# usb_r2.net
KiCad netlist of a schematic drawn in EAGLE
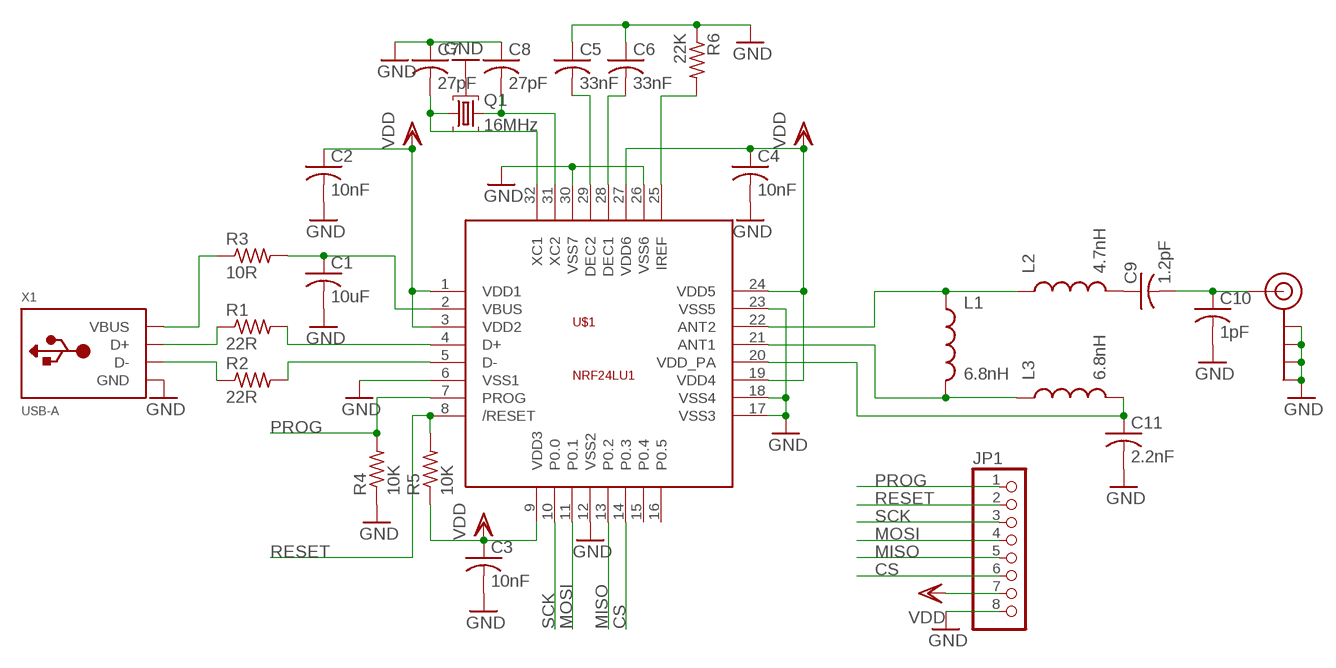
[diagram p0: schematic, sheet 1]

(export (version "E")
  (design (tool "Eeschema 10.0.6"))
  (components
    (comp (ref "C1")
      (value "10uF")
      (footprint "eagle-import:C0805K")
      (libsource (lib "eagle-import") (part "C-USC0805K"))
    )
    (comp (ref "C2")
      (value "10nF")
      (footprint "eagle-import:C0402")
      (libsource (lib "eagle-import") (part "C-USC0402"))
    )
    (comp (ref "C3")
      (value "10nF")
      (footprint "eagle-import:C0402")
      (libsource (lib "eagle-import") (part "C-USC0402"))
    )
    (comp (ref "C4")
      (value "10nF")
      (footprint "eagle-import:C0402")
      (libsource (lib "eagle-import") (part "C-USC0402"))
    )
    (comp (ref "C5")
      (value "33nF")
      (footprint "eagle-import:C0402")
      (libsource (lib "eagle-import") (part "C-USC0402"))
    )
    (comp (ref "C6")
      (value "33nF")
      (footprint "eagle-import:C0402")
      (libsource (lib "eagle-import") (part "C-USC0402"))
    )
    (comp (ref "C7")
      (value "27pF")
      (footprint "eagle-import:C0402")
      (libsource (lib "eagle-import") (part "C-USC0402"))
    )
    (comp (ref "C8")
      (value "27pF")
      (footprint "eagle-import:C0402")
      (libsource (lib "eagle-import") (part "C-USC0402"))
    )
    (comp (ref "C9")
      (value "1.2pF")
      (footprint "eagle-import:C0402")
      (libsource (lib "eagle-import") (part "C-USC0402"))
    )
    (comp (ref "C10")
      (value "1pF")
      (footprint "eagle-import:C0402")
      (libsource (lib "eagle-import") (part "C-USC0402"))
    )
    (comp (ref "C11")
      (value "2.2nF")
      (footprint "eagle-import:C0402")
      (libsource (lib "eagle-import") (part "C-USC0402"))
    )
    (comp (ref "J$1")
      (value "SMA_EDGE")
      (footprint "eagle-import:SMA-EDGE")
      (libsource (lib "eagle-import") (part "SMA_EDGE"))
    )
    (comp (ref "JP1")
      (value "PINHD-1X8")
      (footprint "eagle-import:1X08")
      (libsource (lib "eagle-import") (part "PINHD-1X8"))
    )
    (comp (ref "L1")
      (value "6.8nH")
      (footprint "eagle-import:C0402")
      (libsource (lib "eagle-import") (part "INDUCTOR0402"))
    )
    (comp (ref "L2")
      (value "4.7nH")
      (footprint "eagle-import:C0402")
      (libsource (lib "eagle-import") (part "INDUCTOR0402"))
    )
    (comp (ref "L3")
      (value "6.8nH")
      (footprint "eagle-import:C0402")
      (libsource (lib "eagle-import") (part "INDUCTOR0402"))
    )
    (comp (ref "Q1")
      (value "16MHz")
      (footprint "eagle-import:TSX-3225")
      (libsource (lib "eagle-import") (part "TSX-3225"))
    )
    (comp (ref "R1")
      (value "22R")
      (footprint "eagle-import:R0402")
      (libsource (lib "eagle-import") (part "R-US_R0402"))
    )
    (comp (ref "R2")
      (value "22R")
      (footprint "eagle-import:R0402")
      (libsource (lib "eagle-import") (part "R-US_R0402"))
    )
    (comp (ref "R3")
      (value "10R")
      (footprint "eagle-import:R0402")
      (libsource (lib "eagle-import") (part "R-US_R0402"))
    )
    (comp (ref "R4")
      (value "10K")
      (footprint "eagle-import:R0402")
      (libsource (lib "eagle-import") (part "R-US_R0402"))
    )
    (comp (ref "R5")
      (value "10K")
      (footprint "eagle-import:R0402")
      (libsource (lib "eagle-import") (part "R-US_R0402"))
    )
    (comp (ref "R6")
      (value "22K")
      (footprint "eagle-import:R0402")
      (libsource (lib "eagle-import") (part "R-US_R0402"))
    )
    (comp (ref "U$1")
      (value "NRF24LU1")
      (footprint "eagle-import:QFN-32")
      (libsource (lib "eagle-import") (part "NRF24LU1"))
    )
    (comp (ref "X1")
      (value "USB-A")
      (footprint "eagle-import:MOLEX_480371000")
      (libsource (lib "eagle-import") (part "USB-A"))
    )
  )
  (nets
    (net (code "1") (name "/CS") (class "Default")
      (node (ref "JP1") (pin "6") (pinfunction "6_6") (pintype "passive"))
      (node (ref "U$1") (pin "14") (pinfunction "P0.3_14") (pintype "bidirectional"))
    )
    (net (code "2") (name "/MISO") (class "Default")
      (node (ref "JP1") (pin "5") (pinfunction "5_5") (pintype "passive"))
      (node (ref "U$1") (pin "13") (pinfunction "P0.2_13") (pintype "bidirectional"))
    )
    (net (code "3") (name "/MOSI") (class "Default")
      (node (ref "JP1") (pin "4") (pinfunction "4_4") (pintype "passive"))
      (node (ref "U$1") (pin "11") (pinfunction "P0.1_11") (pintype "bidirectional"))
    )
    (net (code "4") (name "/PROG") (class "Default")
      (node (ref "JP1") (pin "1") (pinfunction "1_1") (pintype "passive"))
      (node (ref "R4") (pin "2") (pinfunction "2_2") (pintype "passive"))
      (node (ref "U$1") (pin "7") (pinfunction "PROG_7") (pintype "bidirectional"))
    )
    (net (code "5") (name "/RESET") (class "Default")
      (node (ref "JP1") (pin "2") (pinfunction "2_2") (pintype "passive"))
      (node (ref "R5") (pin "2") (pinfunction "2_2") (pintype "passive"))
      (node (ref "U$1") (pin "8") (pinfunction "/RESET_8") (pintype "bidirectional"))
    )
    (net (code "6") (name "/SCK") (class "Default")
      (node (ref "JP1") (pin "3") (pinfunction "3_3") (pintype "passive"))
      (node (ref "U$1") (pin "10") (pinfunction "P0.0_10") (pintype "bidirectional"))
    )
    (net (code "7") (name "GND") (class "Default")
      (node (ref "C1") (pin "2") (pinfunction "2_2") (pintype "passive"))
      (node (ref "C10") (pin "2") (pinfunction "2_2") (pintype "passive"))
      (node (ref "C11") (pin "2") (pinfunction "2_2") (pintype "passive"))
      (node (ref "C2") (pin "2") (pinfunction "2_2") (pintype "passive"))
      (node (ref "C3") (pin "2") (pinfunction "2_2") (pintype "passive"))
      (node (ref "C4") (pin "2") (pinfunction "2_2") (pintype "passive"))
      (node (ref "C5") (pin "1") (pinfunction "1_1") (pintype "passive"))
      (node (ref "C6") (pin "1") (pinfunction "1_1") (pintype "passive"))
      (node (ref "C7") (pin "1") (pinfunction "1_1") (pintype "passive"))
      (node (ref "C8") (pin "1") (pinfunction "1_1") (pintype "passive"))
      (node (ref "J$1") (pin "GND@0") (pinfunction "GND_GND@0") (pintype "bidirectional"))
      (node (ref "J$1") (pin "GND@1") (pinfunction "GND_GND@1") (pintype "bidirectional"))
      (node (ref "J$1") (pin "GND@2") (pinfunction "GND_GND@2") (pintype "bidirectional"))
      (node (ref "J$1") (pin "GND@3") (pinfunction "GND_GND@3") (pintype "bidirectional"))
      (node (ref "JP1") (pin "8") (pinfunction "8_8") (pintype "passive"))
      (node (ref "Q1") (pin "2") (pinfunction "3_2") (pintype "passive"))
      (node (ref "Q1") (pin "4") (pinfunction "3_4") (pintype "passive"))
      (node (ref "R4") (pin "1") (pinfunction "1_1") (pintype "passive"))
      (node (ref "R6") (pin "1") (pinfunction "1_1") (pintype "passive"))
      (node (ref "U$1") (pin "12") (pinfunction "VSS2_12") (pintype "bidirectional"))
      (node (ref "U$1") (pin "17") (pinfunction "VSS3_17") (pintype "bidirectional"))
      (node (ref "U$1") (pin "18") (pinfunction "VSS4_18") (pintype "bidirectional"))
      (node (ref "U$1") (pin "23") (pinfunction "VSS5_23") (pintype "bidirectional"))
      (node (ref "U$1") (pin "26") (pinfunction "VSS6_26") (pintype "bidirectional"))
      (node (ref "U$1") (pin "30") (pinfunction "VSS7_30") (pintype "bidirectional"))
      (node (ref "U$1") (pin "6") (pinfunction "VSS1_6") (pintype "bidirectional"))
      (node (ref "X1") (pin "4") (pinfunction "GND_4") (pintype "power_in"))
    )
    (net (code "8") (name "Net-(C9-Pad1)") (class "Default")
      (node (ref "C9") (pin "1") (pinfunction "1_1") (pintype "passive"))
      (node (ref "L2") (pin "2") (pinfunction "2_2") (pintype "passive"))
    )
    (net (code "9") (name "Net-(J$1-SIGNAL)") (class "Default")
      (node (ref "C10") (pin "1") (pinfunction "1_1") (pintype "passive"))
      (node (ref "C9") (pin "2") (pinfunction "2_2") (pintype "passive"))
      (node (ref "J$1") (pin "SIG") (pinfunction "SIGNAL_SIG") (pintype "bidirectional"))
    )
    (net (code "10") (name "Net-(Q1-2)") (class "Default")
      (node (ref "C8") (pin "2") (pinfunction "2_2") (pintype "passive"))
      (node (ref "Q1") (pin "3") (pinfunction "2_3") (pintype "passive"))
      (node (ref "U$1") (pin "31") (pinfunction "XC2_31") (pintype "bidirectional"))
    )
    (net (code "11") (name "Net-(U$1-ANT1)") (class "Default")
      (node (ref "L1") (pin "2") (pinfunction "2_2") (pintype "passive"))
      (node (ref "L3") (pin "1") (pinfunction "1_1") (pintype "passive"))
      (node (ref "U$1") (pin "21") (pinfunction "ANT1_21") (pintype "bidirectional"))
    )
    (net (code "12") (name "Net-(U$1-ANT2)") (class "Default")
      (node (ref "L1") (pin "1") (pinfunction "1_1") (pintype "passive"))
      (node (ref "L2") (pin "1") (pinfunction "1_1") (pintype "passive"))
      (node (ref "U$1") (pin "22") (pinfunction "ANT2_22") (pintype "bidirectional"))
    )
    (net (code "13") (name "Net-(U$1-D+)") (class "Default")
      (node (ref "R1") (pin "2") (pinfunction "2_2") (pintype "passive"))
      (node (ref "U$1") (pin "4") (pinfunction "D+_4") (pintype "bidirectional"))
    )
    (net (code "14") (name "Net-(U$1-D-)") (class "Default")
      (node (ref "R2") (pin "2") (pinfunction "2_2") (pintype "passive"))
      (node (ref "U$1") (pin "5") (pinfunction "D-_5") (pintype "bidirectional"))
    )
    (net (code "15") (name "Net-(U$1-DEC1)") (class "Default")
      (node (ref "C6") (pin "2") (pinfunction "2_2") (pintype "passive"))
      (node (ref "U$1") (pin "28") (pinfunction "DEC1_28") (pintype "bidirectional"))
    )
    (net (code "16") (name "Net-(U$1-DEC2)") (class "Default")
      (node (ref "C5") (pin "2") (pinfunction "2_2") (pintype "passive"))
      (node (ref "U$1") (pin "29") (pinfunction "DEC2_29") (pintype "bidirectional"))
    )
    (net (code "17") (name "Net-(U$1-IREF)") (class "Default")
      (node (ref "R6") (pin "2") (pinfunction "2_2") (pintype "passive"))
      (node (ref "U$1") (pin "25") (pinfunction "IREF_25") (pintype "bidirectional"))
    )
    (net (code "18") (name "Net-(U$1-VBUS)") (class "Default")
      (node (ref "C1") (pin "1") (pinfunction "1_1") (pintype "passive"))
      (node (ref "R3") (pin "2") (pinfunction "2_2") (pintype "passive"))
      (node (ref "U$1") (pin "2") (pinfunction "VBUS_2") (pintype "bidirectional"))
    )
    (net (code "19") (name "Net-(U$1-VDD_PA)") (class "Default")
      (node (ref "C11") (pin "1") (pinfunction "1_1") (pintype "passive"))
      (node (ref "L3") (pin "2") (pinfunction "2_2") (pintype "passive"))
      (node (ref "U$1") (pin "20") (pinfunction "VDD_PA_20") (pintype "bidirectional"))
    )
    (net (code "20") (name "Net-(U$1-XC1)") (class "Default")
      (node (ref "C7") (pin "2") (pinfunction "2_2") (pintype "passive"))
      (node (ref "Q1") (pin "1") (pinfunction "1_1") (pintype "passive"))
      (node (ref "U$1") (pin "32") (pinfunction "XC1_32") (pintype "bidirectional"))
    )
    (net (code "21") (name "Net-(X1-D+)") (class "Default")
      (node (ref "R1") (pin "1") (pinfunction "1_1") (pintype "passive"))
      (node (ref "X1") (pin "3") (pinfunction "D+_3") (pintype "bidirectional"))
    )
    (net (code "22") (name "Net-(X1-D-)") (class "Default")
      (node (ref "R2") (pin "1") (pinfunction "1_1") (pintype "passive"))
      (node (ref "X1") (pin "2") (pinfunction "D-_2") (pintype "bidirectional"))
    )
    (net (code "23") (name "Net-(X1-VBUS)") (class "Default")
      (node (ref "R3") (pin "1") (pinfunction "1_1") (pintype "passive"))
      (node (ref "X1") (pin "1") (pinfunction "VBUS_1") (pintype "power_in"))
    )
    (net (code "24") (name "VDD") (class "Default")
      (node (ref "C2") (pin "1") (pinfunction "1_1") (pintype "passive"))
      (node (ref "C3") (pin "1") (pinfunction "1_1") (pintype "passive"))
      (node (ref "C4") (pin "1") (pinfunction "1_1") (pintype "passive"))
      (node (ref "JP1") (pin "7") (pinfunction "7_7") (pintype "passive"))
      (node (ref "R5") (pin "1") (pinfunction "1_1") (pintype "passive"))
      (node (ref "U$1") (pin "1") (pinfunction "VDD1_1") (pintype "bidirectional"))
      (node (ref "U$1") (pin "19") (pinfunction "VDD4_19") (pintype "bidirectional"))
      (node (ref "U$1") (pin "24") (pinfunction "VDD5_24") (pintype "bidirectional"))
      (node (ref "U$1") (pin "27") (pinfunction "VDD6_27") (pintype "bidirectional"))
      (node (ref "U$1") (pin "3") (pinfunction "VDD2_3") (pintype "bidirectional"))
      (node (ref "U$1") (pin "9") (pinfunction "VDD3_9") (pintype "bidirectional"))
    )
    (net (code "25") (name "unconnected-(U$1-P0.4-Pad15)") (class "Default")
      (node (ref "U$1") (pin "15") (pinfunction "P0.4_15") (pintype "bidirectional"))
    )
    (net (code "26") (name "unconnected-(U$1-P0.5-Pad16)") (class "Default")
      (node (ref "U$1") (pin "16") (pinfunction "P0.5_16") (pintype "bidirectional"))
    )
  )
)
